# pic16f1619_LCD16x02_I2C.net
KiCad netlist of a schematic drawn in EAGLE
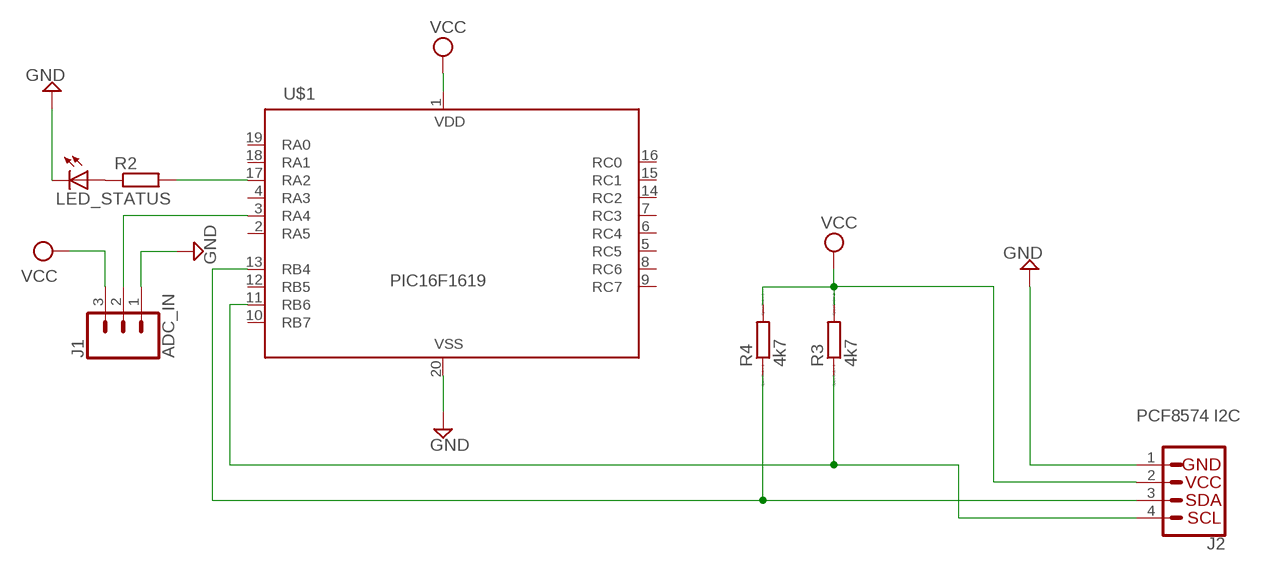
[diagram p0: schematic, sheet 1]

(export (version "E")
  (design (tool "Eeschema 10.0.6"))
  (components
    (comp (ref "J1")
      (value "ADC_IN")
      (footprint "eagle-import:1X03_LOCK")
      (libsource (lib "eagle-import") (part "CONN_03LOCK"))
    )
    (comp (ref "J2")
      (value "PCF8574 I2C")
      (footprint "eagle-import:1X04")
      (libsource (lib "eagle-import") (part "I2C_STANDARD"))
    )
    (comp (ref "LED_STATUS")
      (value "LEDB155")
      (footprint "eagle-import:Q62902-B155")
      (libsource (lib "eagle-import") (part "LEDB155"))
    )
    (comp (ref "R2")
      (value "R-EU_0309/V")
      (footprint "eagle-import:0309V")
      (libsource (lib "eagle-import") (part "R-EU_0309/V"))
    )
    (comp (ref "R3")
      (value "4k7")
      (footprint "eagle-import:R2010")
      (libsource (lib "eagle-import") (part "RR2010"))
    )
    (comp (ref "R4")
      (value "4k7")
      (footprint "eagle-import:R2010")
      (libsource (lib "eagle-import") (part "RR2010"))
    )
    (comp (ref "U$1")
      (value "PIC16F1619")
      (footprint "eagle-import:DIP20B")
      (libsource (lib "eagle-import") (part "PIC16F1619-DIP"))
    )
  )
  (nets
    (net (code "1") (name "GND") (class "Default")
      (node (ref "J1") (pin "1") (pinfunction "1_1") (pintype "passive"))
      (node (ref "J2") (pin "1") (pinfunction "1_1") (pintype "power_in"))
      (node (ref "LED_STATUS") (pin "K") (pinfunction "C_K") (pintype "passive"))
      (node (ref "U$1") (pin "20") (pinfunction "VSS_20") (pintype "power_in"))
    )
    (net (code "2") (name "Net-(LED_STATUS-PadA)") (class "Default")
      (node (ref "LED_STATUS") (pin "A") (pinfunction "A_A") (pintype "passive"))
      (node (ref "R2") (pin "1") (pinfunction "1_1") (pintype "passive"))
    )
    (net (code "3") (name "Net-(U$1-RA2)") (class "Default")
      (node (ref "R2") (pin "2") (pinfunction "2_2") (pintype "passive"))
      (node (ref "U$1") (pin "17") (pinfunction "RA2_17") (pintype "bidirectional"))
    )
    (net (code "4") (name "Net-(U$1-RA4)") (class "Default")
      (node (ref "J1") (pin "2") (pinfunction "2_2") (pintype "passive"))
      (node (ref "U$1") (pin "3") (pinfunction "RA4_3") (pintype "bidirectional"))
    )
    (net (code "5") (name "Net-(U$1-RB4)") (class "Default")
      (node (ref "J2") (pin "3") (pinfunction "3_3") (pintype "passive"))
      (node (ref "R4") (pin "1") (pinfunction "1_1") (pintype "passive"))
      (node (ref "U$1") (pin "13") (pinfunction "RB4_13") (pintype "bidirectional"))
    )
    (net (code "6") (name "Net-(U$1-RB6)") (class "Default")
      (node (ref "J2") (pin "4") (pinfunction "4_4") (pintype "passive"))
      (node (ref "R3") (pin "1") (pinfunction "1_1") (pintype "passive"))
      (node (ref "U$1") (pin "11") (pinfunction "RB6_11") (pintype "bidirectional"))
    )
    (net (code "7") (name "VCC") (class "Default")
      (node (ref "J1") (pin "3") (pinfunction "3_3") (pintype "passive"))
      (node (ref "J2") (pin "2") (pinfunction "2_2") (pintype "power_in"))
      (node (ref "R3") (pin "2") (pinfunction "2_2") (pintype "passive"))
      (node (ref "R4") (pin "2") (pinfunction "2_2") (pintype "passive"))
      (node (ref "U$1") (pin "1") (pinfunction "VDD_1") (pintype "power_in"))
    )
    (net (code "8") (name "unconnected-(U$1-RA0-Pad19)") (class "Default")
      (node (ref "U$1") (pin "19") (pinfunction "RA0_19") (pintype "bidirectional"))
    )
    (net (code "9") (name "unconnected-(U$1-RA1-Pad18)") (class "Default")
      (node (ref "U$1") (pin "18") (pinfunction "RA1_18") (pintype "bidirectional"))
    )
    (net (code "10") (name "unconnected-(U$1-RA3-Pad4)") (class "Default")
      (node (ref "U$1") (pin "4") (pinfunction "RA3_4") (pintype "input"))
    )
    (net (code "11") (name "unconnected-(U$1-RA5-Pad2)") (class "Default")
      (node (ref "U$1") (pin "2") (pinfunction "RA5_2") (pintype "bidirectional"))
    )
    (net (code "12") (name "unconnected-(U$1-RB5-Pad12)") (class "Default")
      (node (ref "U$1") (pin "12") (pinfunction "RB5_12") (pintype "bidirectional"))
    )
    (net (code "13") (name "unconnected-(U$1-RB7-Pad10)") (class "Default")
      (node (ref "U$1") (pin "10") (pinfunction "RB7_10") (pintype "bidirectional"))
    )
    (net (code "14") (name "unconnected-(U$1-RC0-Pad16)") (class "Default")
      (node (ref "U$1") (pin "16") (pinfunction "RC0_16") (pintype "bidirectional"))
    )
    (net (code "15") (name "unconnected-(U$1-RC1-Pad15)") (class "Default")
      (node (ref "U$1") (pin "15") (pinfunction "RC1_15") (pintype "bidirectional"))
    )
    (net (code "16") (name "unconnected-(U$1-RC2-Pad14)") (class "Default")
      (node (ref "U$1") (pin "14") (pinfunction "RC2_14") (pintype "bidirectional"))
    )
    (net (code "17") (name "unconnected-(U$1-RC3-Pad7)") (class "Default")
      (node (ref "U$1") (pin "7") (pinfunction "RC3_7") (pintype "bidirectional"))
    )
    (net (code "18") (name "unconnected-(U$1-RC4-Pad6)") (class "Default")
      (node (ref "U$1") (pin "6") (pinfunction "RC4_6") (pintype "bidirectional"))
    )
    (net (code "19") (name "unconnected-(U$1-RC5-Pad5)") (class "Default")
      (node (ref "U$1") (pin "5") (pinfunction "RC5_5") (pintype "bidirectional"))
    )
    (net (code "20") (name "unconnected-(U$1-RC6-Pad8)") (class "Default")
      (node (ref "U$1") (pin "8") (pinfunction "RC6_8") (pintype "bidirectional"))
    )
    (net (code "21") (name "unconnected-(U$1-RC7-Pad9)") (class "Default")
      (node (ref "U$1") (pin "9") (pinfunction "RC7_9") (pintype "bidirectional"))
    )
  )
)
